# barebonesarduino.net
KiCad netlist of a schematic drawn in EAGLE
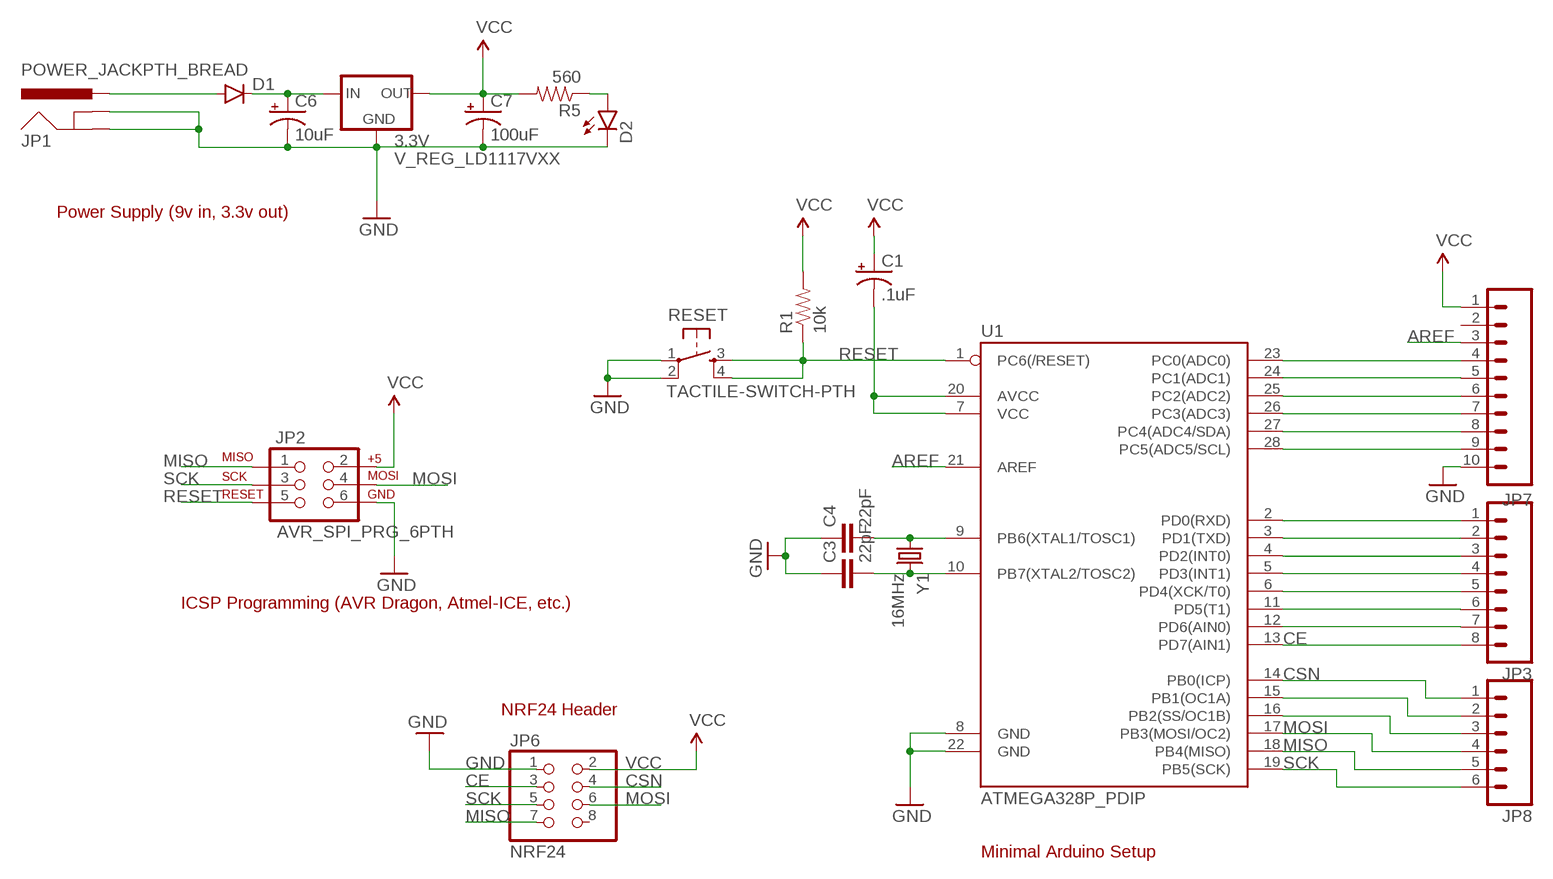
[diagram p0: schematic, sheet 1]

(export (version "E")
  (design (tool "Eeschema 10.0.6"))
  (components
    (comp (ref "3.3V")
      (value "V_REG_LD1117VXX")
      (footprint "eagle-import:78XXL")
      (libsource (lib "eagle-import") (part "V_REG_LD1117VXX"))
    )
    (comp (ref "C1")
      (value ".1uF")
      (footprint "eagle-import:CPOL-RADIAL-100UF-25V")
      (libsource (lib "eagle-import") (part "CAP_POLPTH1"))
    )
    (comp (ref "C3")
      (value "22pF")
      (footprint "eagle-import:CAP-PTH-SMALL")
      (libsource (lib "eagle-import") (part "CAPPTH"))
    )
    (comp (ref "C4")
      (value "22pF")
      (footprint "eagle-import:CAP-PTH-SMALL")
      (libsource (lib "eagle-import") (part "CAPPTH"))
    )
    (comp (ref "C6")
      (value "10uF")
      (footprint "eagle-import:CPOL-RADIAL-100UF-25V")
      (libsource (lib "eagle-import") (part "CAP_POLPTH1"))
    )
    (comp (ref "C7")
      (value "100uF")
      (footprint "eagle-import:CPOL-RADIAL-100UF-25V")
      (libsource (lib "eagle-import") (part "CAP_POLPTH1"))
    )
    (comp (ref "D1")
      (value "DIODEPTH")
      (footprint "eagle-import:DIODE-1N4001")
      (libsource (lib "eagle-import") (part "DIODEPTH"))
    )
    (comp (ref "D2")
      (value "LED5MM")
      (footprint "eagle-import:LED5MM")
      (libsource (lib "eagle-import") (part "LED5MM"))
    )
    (comp (ref "JP1")
      (value "POWER_JACKPTH_BREAD")
      (footprint "eagle-import:POWER_JACK_PTH_BREAD")
      (libsource (lib "eagle-import") (part "POWER_JACKPTH_BREAD"))
    )
    (comp (ref "JP2")
      (value "AVR_SPI_PRG_6PTH")
      (footprint "eagle-import:2X3")
      (libsource (lib "eagle-import") (part "AVR_SPI_PRG_6PTH"))
    )
    (comp (ref "JP3")
      (value "M08NO_SILK_FEMALE_PTH")
      (footprint "eagle-import:1X08_NO_SILK")
      (libsource (lib "eagle-import") (part "M08NO_SILK_FEMALE_PTH"))
    )
    (comp (ref "JP6")
      (value "NRF24")
      (footprint "eagle-import:2X04")
      (libsource (lib "eagle-import") (part "PINHD-2X4"))
    )
    (comp (ref "JP7")
      (value "M10NO_SILK_PTH_FEMALE")
      (footprint "eagle-import:1X10_NO_SILK")
      (libsource (lib "eagle-import") (part "M10NO_SILK_PTH_FEMALE"))
    )
    (comp (ref "JP8")
      (value "M06NO_SILK_YES_STOP")
      (footprint "eagle-import:1X06_NO_SILK_YES_STOP")
      (libsource (lib "eagle-import") (part "M06NO_SILK_YES_STOP"))
    )
    (comp (ref "R1")
      (value "10k")
      (footprint "eagle-import:AXIAL-0.4")
      (libsource (lib "eagle-import") (part "RESISTORPTH-1/4W"))
    )
    (comp (ref "R5")
      (value "560")
      (footprint "eagle-import:AXIAL-0.4")
      (libsource (lib "eagle-import") (part "RESISTORPTH-1/4W"))
    )
    (comp (ref "RESET")
      (value "TACTILE-SWITCH-PTH")
      (footprint "eagle-import:TAC-SWITCH-PTH")
      (libsource (lib "eagle-import") (part "TACTILE-SWITCH-PTH"))
    )
    (comp (ref "U1")
      (value "ATMEGA328P_PDIP")
      (footprint "eagle-import:DIL28-3")
      (libsource (lib "eagle-import") (part "ATMEGA328P_PDIP"))
    )
    (comp (ref "Y1")
      (value "16MHz")
      (footprint "eagle-import:HC49US")
      (libsource (lib "eagle-import") (part "CRYSTALHC49US"))
    )
  )
  (nets
    (net (code "1") (name "/AREF") (class "Default")
      (node (ref "JP7") (pin "3") (pinfunction "3_3") (pintype "passive"))
      (node (ref "U1") (pin "21") (pinfunction "AREF_21") (pintype "bidirectional"))
    )
    (net (code "2") (name "/CE") (class "Default")
      (node (ref "JP3") (pin "8") (pinfunction "8_8") (pintype "passive"))
      (node (ref "JP6") (pin "3") (pinfunction "3_3") (pintype "passive"))
      (node (ref "U1") (pin "13") (pinfunction "PD7(AIN1)_13") (pintype "bidirectional"))
    )
    (net (code "3") (name "/CSN") (class "Default")
      (node (ref "JP6") (pin "4") (pinfunction "4_4") (pintype "passive"))
      (node (ref "JP8") (pin "1") (pinfunction "1_1") (pintype "passive"))
      (node (ref "U1") (pin "14") (pinfunction "PB0(ICP)_14") (pintype "bidirectional"))
    )
    (net (code "4") (name "/MISO") (class "Default")
      (node (ref "JP2") (pin "1") (pinfunction "1_1") (pintype "passive"))
      (node (ref "JP6") (pin "7") (pinfunction "7_7") (pintype "passive"))
      (node (ref "JP8") (pin "5") (pinfunction "5_5") (pintype "passive"))
      (node (ref "U1") (pin "18") (pinfunction "PB4(MISO)_18") (pintype "bidirectional"))
    )
    (net (code "5") (name "/MOSI") (class "Default")
      (node (ref "JP2") (pin "4") (pinfunction "4_4") (pintype "passive"))
      (node (ref "JP6") (pin "6") (pinfunction "6_6") (pintype "passive"))
      (node (ref "JP8") (pin "4") (pinfunction "4_4") (pintype "passive"))
      (node (ref "U1") (pin "17") (pinfunction "PB3(MOSI/OC2)_17") (pintype "bidirectional"))
    )
    (net (code "6") (name "/RESET") (class "Default")
      (node (ref "JP2") (pin "5") (pinfunction "5_5") (pintype "passive"))
      (node (ref "R1") (pin "P$1") (pinfunction "1_P$1") (pintype "passive"))
      (node (ref "RESET") (pin "3") (pinfunction "3_3") (pintype "passive"))
      (node (ref "RESET") (pin "4") (pinfunction "4_4") (pintype "passive"))
      (node (ref "U1") (pin "1") (pinfunction "PC6(/RESET)_1") (pintype "bidirectional"))
    )
    (net (code "7") (name "/SCK") (class "Default")
      (node (ref "JP2") (pin "3") (pinfunction "3_3") (pintype "passive"))
      (node (ref "JP6") (pin "5") (pinfunction "5_5") (pintype "passive"))
      (node (ref "JP8") (pin "6") (pinfunction "6_6") (pintype "passive"))
      (node (ref "U1") (pin "19") (pinfunction "PB5(SCK)_19") (pintype "bidirectional"))
    )
    (net (code "8") (name "GND") (class "Default")
      (node (ref "3.3V") (pin "IN") (pinfunction "GND_IN") (pintype "input"))
      (node (ref "C3") (pin "1") (pinfunction "1_1") (pintype "passive"))
      (node (ref "C4") (pin "1") (pinfunction "1_1") (pintype "passive"))
      (node (ref "C6") (pin "2") (pinfunction "-_2") (pintype "passive"))
      (node (ref "C7") (pin "2") (pinfunction "-_2") (pintype "passive"))
      (node (ref "D2") (pin "K") (pinfunction "C_K") (pintype "passive"))
      (node (ref "JP1") (pin "GND") (pinfunction "GND_GND") (pintype "bidirectional"))
      (node (ref "JP1") (pin "GNDBREAK") (pinfunction "GNDBREAK_GNDBREAK") (pintype "bidirectional"))
      (node (ref "JP2") (pin "6") (pinfunction "6_6") (pintype "passive"))
      (node (ref "JP6") (pin "1") (pinfunction "1_1") (pintype "passive"))
      (node (ref "JP7") (pin "10") (pinfunction "10_10") (pintype "passive"))
      (node (ref "RESET") (pin "1") (pinfunction "1_1") (pintype "passive"))
      (node (ref "RESET") (pin "2") (pinfunction "2_2") (pintype "passive"))
      (node (ref "U1") (pin "22") (pinfunction "GND_22") (pintype "bidirectional"))
      (node (ref "U1") (pin "8") (pinfunction "GND_8") (pintype "bidirectional"))
    )
    (net (code "9") (name "Net-(3.3V-IN)") (class "Default")
      (node (ref "3.3V") (pin "OUT") (pinfunction "IN_OUT") (pintype "input"))
      (node (ref "C6") (pin "1") (pinfunction "+_1") (pintype "passive"))
      (node (ref "D1") (pin "C") (pinfunction "C_C") (pintype "passive"))
    )
    (net (code "10") (name "Net-(C1--)") (class "Default")
      (node (ref "C1") (pin "2") (pinfunction "-_2") (pintype "passive"))
      (node (ref "U1") (pin "20") (pinfunction "AVCC_20") (pintype "bidirectional"))
      (node (ref "U1") (pin "7") (pinfunction "VCC_7") (pintype "bidirectional"))
    )
    (net (code "11") (name "Net-(D1-PadA)") (class "Default")
      (node (ref "D1") (pin "A") (pinfunction "A_A") (pintype "passive"))
      (node (ref "JP1") (pin "PWR") (pinfunction "PWR_PWR") (pintype "bidirectional"))
    )
    (net (code "12") (name "Net-(R5-1)") (class "Default")
      (node (ref "D2") (pin "A") (pinfunction "A_A") (pintype "passive"))
      (node (ref "R5") (pin "P$1") (pinfunction "1_P$1") (pintype "passive"))
    )
    (net (code "13") (name "Net-(U1-PB1(OC1A))") (class "Default")
      (node (ref "JP8") (pin "2") (pinfunction "2_2") (pintype "passive"))
      (node (ref "U1") (pin "15") (pinfunction "PB1(OC1A)_15") (pintype "bidirectional"))
    )
    (net (code "14") (name "Net-(U1-PB2(SS{slash}OC1B))") (class "Default")
      (node (ref "JP8") (pin "3") (pinfunction "3_3") (pintype "passive"))
      (node (ref "U1") (pin "16") (pinfunction "PB2(SS/OC1B)_16") (pintype "bidirectional"))
    )
    (net (code "15") (name "Net-(U1-PB6(XTAL1{slash}TOSC1))") (class "Default")
      (node (ref "C4") (pin "2") (pinfunction "2_2") (pintype "passive"))
      (node (ref "U1") (pin "9") (pinfunction "PB6(XTAL1/TOSC1)_9") (pintype "bidirectional"))
      (node (ref "Y1") (pin "1") (pinfunction "1_1") (pintype "passive"))
    )
    (net (code "16") (name "Net-(U1-PB7(XTAL2{slash}TOSC2))") (class "Default")
      (node (ref "C3") (pin "2") (pinfunction "2_2") (pintype "passive"))
      (node (ref "U1") (pin "10") (pinfunction "PB7(XTAL2/TOSC2)_10") (pintype "bidirectional"))
      (node (ref "Y1") (pin "2") (pinfunction "2_2") (pintype "passive"))
    )
    (net (code "17") (name "Net-(U1-PC0(ADC0))") (class "Default")
      (node (ref "JP7") (pin "4") (pinfunction "4_4") (pintype "passive"))
      (node (ref "U1") (pin "23") (pinfunction "PC0(ADC0)_23") (pintype "bidirectional"))
    )
    (net (code "18") (name "Net-(U1-PC1(ADC1))") (class "Default")
      (node (ref "JP7") (pin "5") (pinfunction "5_5") (pintype "passive"))
      (node (ref "U1") (pin "24") (pinfunction "PC1(ADC1)_24") (pintype "bidirectional"))
    )
    (net (code "19") (name "Net-(U1-PC2(ADC2))") (class "Default")
      (node (ref "JP7") (pin "6") (pinfunction "6_6") (pintype "passive"))
      (node (ref "U1") (pin "25") (pinfunction "PC2(ADC2)_25") (pintype "bidirectional"))
    )
    (net (code "20") (name "Net-(U1-PC3(ADC3))") (class "Default")
      (node (ref "JP7") (pin "7") (pinfunction "7_7") (pintype "passive"))
      (node (ref "U1") (pin "26") (pinfunction "PC3(ADC3)_26") (pintype "bidirectional"))
    )
    (net (code "21") (name "Net-(U1-PC4(ADC4{slash}SDA))") (class "Default")
      (node (ref "JP7") (pin "8") (pinfunction "8_8") (pintype "passive"))
      (node (ref "U1") (pin "27") (pinfunction "PC4(ADC4/SDA)_27") (pintype "bidirectional"))
    )
    (net (code "22") (name "Net-(U1-PC5(ADC5{slash}SCL))") (class "Default")
      (node (ref "JP7") (pin "9") (pinfunction "9_9") (pintype "passive"))
      (node (ref "U1") (pin "28") (pinfunction "PC5(ADC5/SCL)_28") (pintype "bidirectional"))
    )
    (net (code "23") (name "Net-(U1-PD0(RXD))") (class "Default")
      (node (ref "JP3") (pin "1") (pinfunction "1_1") (pintype "passive"))
      (node (ref "U1") (pin "2") (pinfunction "PD0(RXD)_2") (pintype "bidirectional"))
    )
    (net (code "24") (name "Net-(U1-PD1(TXD))") (class "Default")
      (node (ref "JP3") (pin "2") (pinfunction "2_2") (pintype "passive"))
      (node (ref "U1") (pin "3") (pinfunction "PD1(TXD)_3") (pintype "bidirectional"))
    )
    (net (code "25") (name "Net-(U1-PD2(INT0))") (class "Default")
      (node (ref "JP3") (pin "3") (pinfunction "3_3") (pintype "passive"))
      (node (ref "U1") (pin "4") (pinfunction "PD2(INT0)_4") (pintype "bidirectional"))
    )
    (net (code "26") (name "Net-(U1-PD3(INT1))") (class "Default")
      (node (ref "JP3") (pin "4") (pinfunction "4_4") (pintype "passive"))
      (node (ref "U1") (pin "5") (pinfunction "PD3(INT1)_5") (pintype "bidirectional"))
    )
    (net (code "27") (name "Net-(U1-PD4(XCK{slash}T0))") (class "Default")
      (node (ref "JP3") (pin "5") (pinfunction "5_5") (pintype "passive"))
      (node (ref "U1") (pin "6") (pinfunction "PD4(XCK/T0)_6") (pintype "bidirectional"))
    )
    (net (code "28") (name "Net-(U1-PD5(T1))") (class "Default")
      (node (ref "JP3") (pin "6") (pinfunction "6_6") (pintype "passive"))
      (node (ref "U1") (pin "11") (pinfunction "PD5(T1)_11") (pintype "bidirectional"))
    )
    (net (code "29") (name "Net-(U1-PD6(AIN0))") (class "Default")
      (node (ref "JP3") (pin "7") (pinfunction "7_7") (pintype "passive"))
      (node (ref "U1") (pin "12") (pinfunction "PD6(AIN0)_12") (pintype "bidirectional"))
    )
    (net (code "30") (name "VCC") (class "Default")
      (node (ref "3.3V") (pin "GND") (pinfunction "OUT_GND") (pintype "passive"))
      (node (ref "C1") (pin "1") (pinfunction "+_1") (pintype "passive"))
      (node (ref "C7") (pin "1") (pinfunction "+_1") (pintype "passive"))
      (node (ref "JP2") (pin "2") (pinfunction "2_2") (pintype "passive"))
      (node (ref "JP6") (pin "2") (pinfunction "2_2") (pintype "passive"))
      (node (ref "JP7") (pin "1") (pinfunction "1_1") (pintype "passive"))
      (node (ref "R1") (pin "P$2") (pinfunction "2_P$2") (pintype "passive"))
      (node (ref "R5") (pin "P$2") (pinfunction "2_P$2") (pintype "passive"))
    )
    (net (code "31") (name "unconnected-(JP6-Pad8)") (class "Default")
      (node (ref "JP6") (pin "8") (pinfunction "8_8") (pintype "passive"))
    )
    (net (code "32") (name "unconnected-(JP7-Pad2)") (class "Default")
      (node (ref "JP7") (pin "2") (pinfunction "2_2") (pintype "passive"))
    )
  )
)
